# PCB_Draft_1.net
KiCad netlist of a schematic drawn in EAGLE
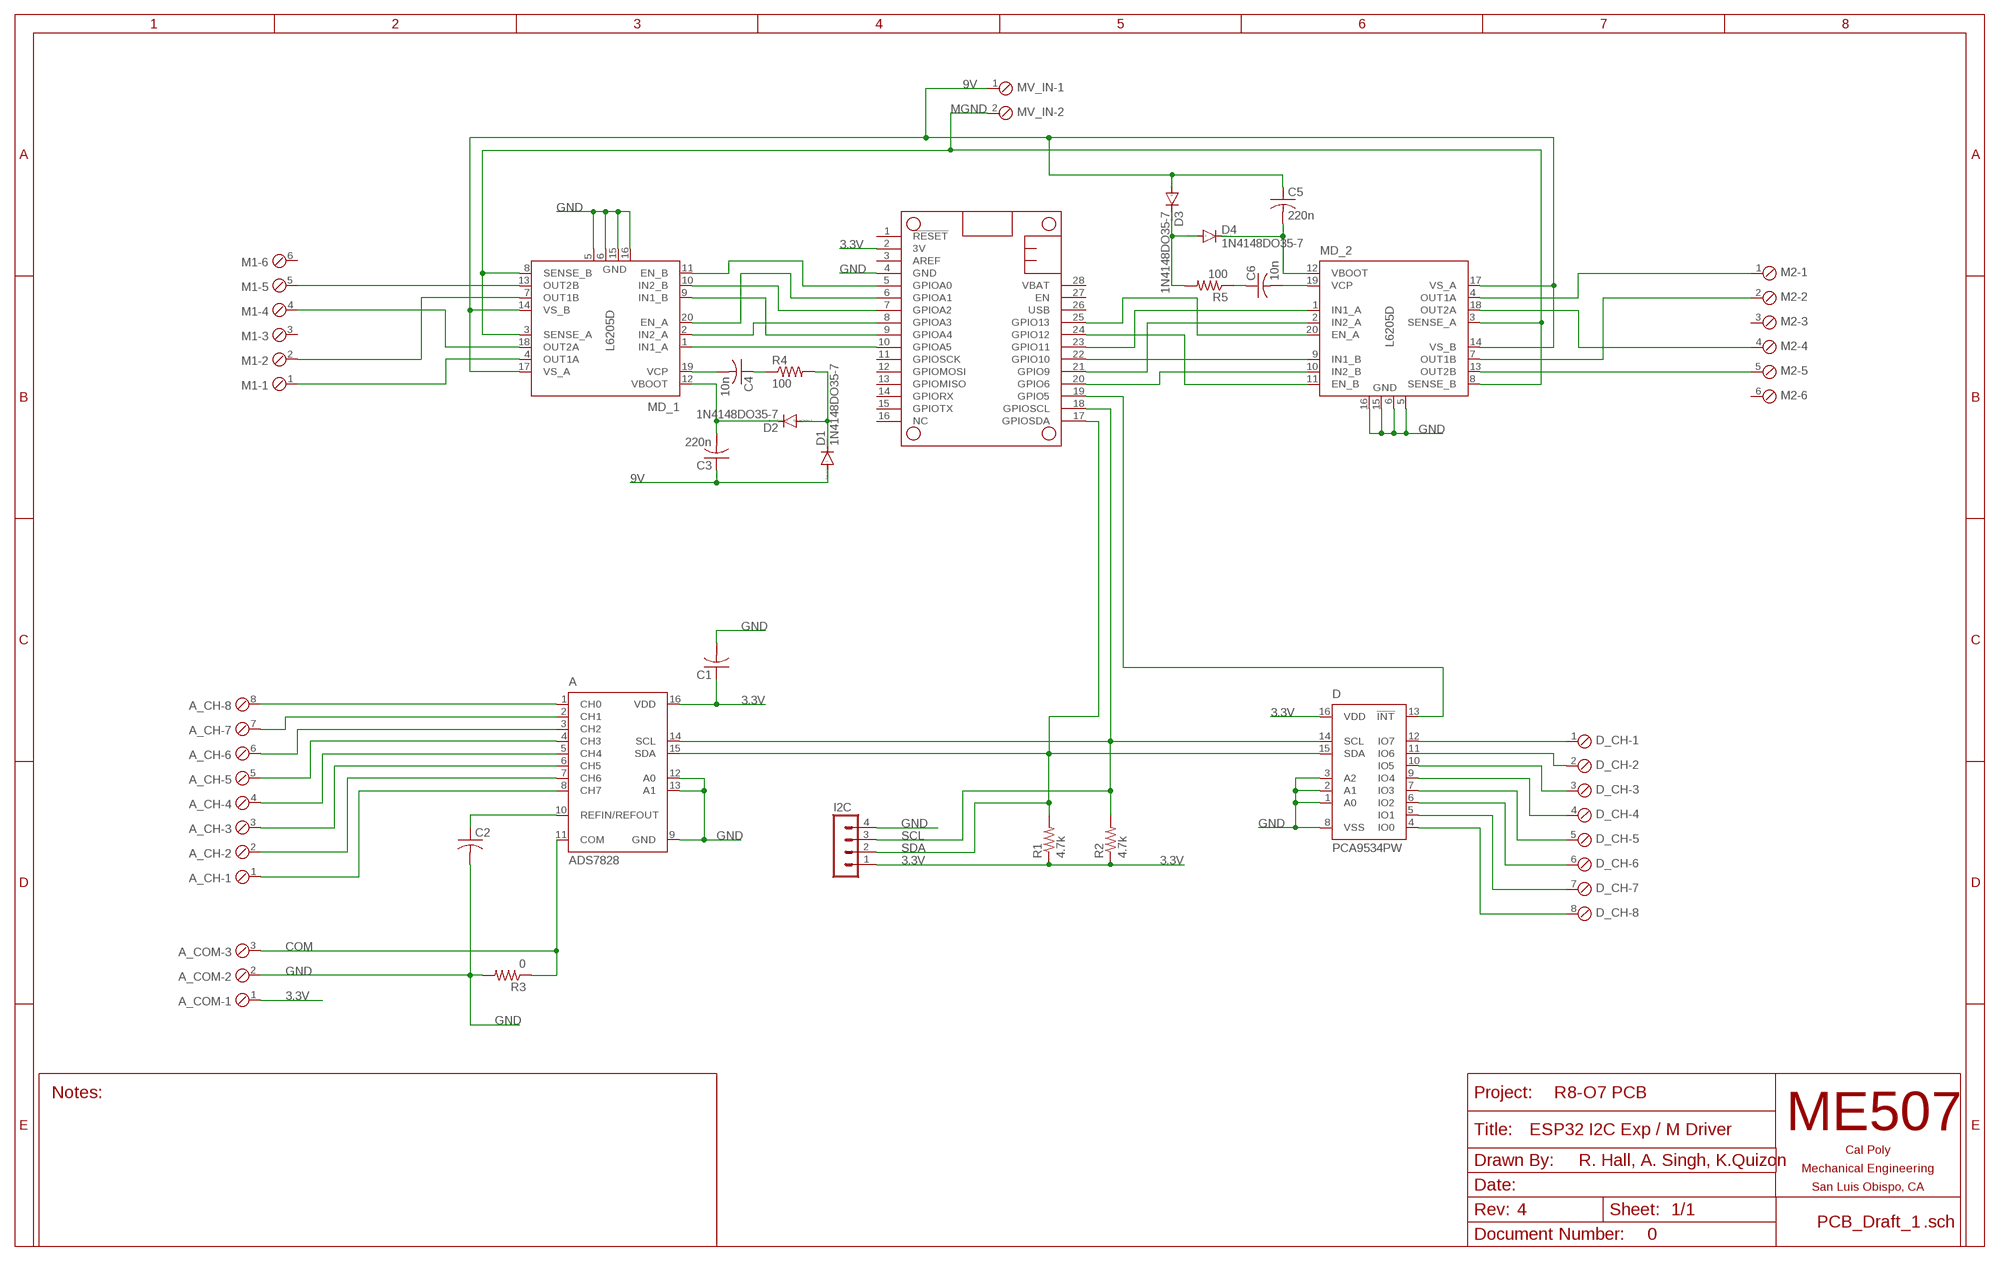
[diagram p0: schematic, sheet 1]

(export (version "E")
  (design (tool "Eeschema 10.0.6"))
  (components
    (comp (ref "A")
      (value "ADS7828")
      (footprint "eagle-import:TSSOP16-PW")
      (fields (field (name "MF") "TEXAS INSTRUMENTS") (field (name "MPN") "ADS7828E/250"))
      (libsource (lib "eagle-import") (part "ADS7828"))
    )
    (comp (ref "A_CH")
      (value "SCREWTERM_8P_254")
      (footprint "eagle-import:8POL254")
      (libsource (lib "eagle-import") (part "SCREWTERM_8P_254"))
    )
    (comp (ref "A_COM")
      (value "SCREWTERM_3P_254")
      (footprint "eagle-import:3POL254")
      (libsource (lib "eagle-import") (part "SCREWTERM_3P_254"))
    )
    (comp (ref "C1")
      (value "C-USC0805")
      (footprint "eagle-import:C0805")
      (libsource (lib "eagle-import") (part "C-USC0805"))
    )
    (comp (ref "C2")
      (value "C-USC0805")
      (footprint "eagle-import:C0805")
      (libsource (lib "eagle-import") (part "C-USC0805"))
    )
    (comp (ref "C3")
      (value "220n")
      (footprint "eagle-import:C0805")
      (libsource (lib "eagle-import") (part "C-USC0805"))
    )
    (comp (ref "C4")
      (value "10n")
      (footprint "eagle-import:C0805")
      (libsource (lib "eagle-import") (part "C-USC0805"))
    )
    (comp (ref "C5")
      (value "220n")
      (footprint "eagle-import:C0805")
      (libsource (lib "eagle-import") (part "C-USC0805"))
    )
    (comp (ref "C6")
      (value "10n")
      (footprint "eagle-import:C0805")
      (libsource (lib "eagle-import") (part "C-USC0805"))
    )
    (comp (ref "D")
      (value "PCA9534PW")
      (footprint "eagle-import:TSSOP16")
      (libsource (lib "eagle-import") (part "PCA9534PW"))
    )
    (comp (ref "D1")
      (value "1N4148DO35-7")
      (footprint "eagle-import:DO35-7")
      (libsource (lib "eagle-import") (part "1N4148DO35-7"))
    )
    (comp (ref "D2")
      (value "1N4148DO35-7")
      (footprint "eagle-import:DO35-7")
      (libsource (lib "eagle-import") (part "1N4148DO35-7"))
    )
    (comp (ref "D3")
      (value "1N4148DO35-7")
      (footprint "eagle-import:DO35-7")
      (libsource (lib "eagle-import") (part "1N4148DO35-7"))
    )
    (comp (ref "D4")
      (value "1N4148DO35-7")
      (footprint "eagle-import:DO35-7")
      (libsource (lib "eagle-import") (part "1N4148DO35-7"))
    )
    (comp (ref "D_CH")
      (value "SCREWTERM_8P_254")
      (footprint "eagle-import:8POL254")
      (libsource (lib "eagle-import") (part "SCREWTERM_8P_254"))
    )
    (comp (ref "FTHRWNG")
      (value "FEATHERWINGEXTENDED_BOTH_ENDS")
      (footprint "eagle-import:FEATHERWING")
      (libsource (lib "eagle-import") (part "FEATHERWINGEXTENDED_BOTH_ENDS"))
    )
    (comp (ref "I2C")
      (value "MA04-1")
      (footprint "eagle-import:MA04-1")
      (libsource (lib "eagle-import") (part "MA04-1"))
    )
    (comp (ref "M1")
      (value "SCREWTERM_6P_254")
      (footprint "eagle-import:6POL254")
      (libsource (lib "eagle-import") (part "SCREWTERM_6P_254"))
    )
    (comp (ref "M2")
      (value "SCREWTERM_6P_254")
      (footprint "eagle-import:6POL254")
      (libsource (lib "eagle-import") (part "SCREWTERM_6P_254"))
    )
    (comp (ref "MD_1")
      (value "L6205D")
      (footprint "eagle-import:SO20")
      (libsource (lib "eagle-import") (part "L6205D"))
    )
    (comp (ref "MD_2")
      (value "L6205D")
      (footprint "eagle-import:SO20")
      (libsource (lib "eagle-import") (part "L6205D"))
    )
    (comp (ref "MV_IN")
      (value "SCREWTERM_2P_254")
      (footprint "eagle-import:2POL254")
      (libsource (lib "eagle-import") (part "SCREWTERM_2P_254"))
    )
    (comp (ref "R1")
      (value "4.7k")
      (footprint "eagle-import:M0805")
      (libsource (lib "eagle-import") (part "R-US_M0805"))
    )
    (comp (ref "R2")
      (value "4.7k")
      (footprint "eagle-import:M0805")
      (libsource (lib "eagle-import") (part "R-US_M0805"))
    )
    (comp (ref "R3")
      (value "0")
      (footprint "eagle-import:M0805")
      (libsource (lib "eagle-import") (part "R-US_M0805"))
    )
    (comp (ref "R4")
      (value "100")
      (footprint "eagle-import:M0805")
      (libsource (lib "eagle-import") (part "R-US_M0805"))
    )
    (comp (ref "R5")
      (value "100")
      (footprint "eagle-import:M0805")
      (libsource (lib "eagle-import") (part "R-US_M0805"))
    )
  )
  (nets
    (net (code "1") (name "/3.3V") (class "Default")
      (node (ref "A") (pin "16") (pinfunction "VDD_16") (pintype "power_in"))
      (node (ref "A_COM") (pin "1") (pinfunction "1_1") (pintype "passive"))
      (node (ref "C1") (pin "1") (pinfunction "1_1") (pintype "passive"))
      (node (ref "D") (pin "16") (pinfunction "VDD_16") (pintype "power_in"))
      (node (ref "FTHRWNG") (pin "2") (pinfunction "3V_2") (pintype "power_in"))
      (node (ref "I2C") (pin "1") (pinfunction "1_1") (pintype "passive"))
      (node (ref "R1") (pin "1") (pinfunction "1_1") (pintype "passive"))
      (node (ref "R2") (pin "1") (pinfunction "1_1") (pintype "passive"))
    )
    (net (code "2") (name "/9V") (class "Default")
      (node (ref "C3") (pin "1") (pinfunction "1_1") (pintype "passive"))
      (node (ref "C5") (pin "1") (pinfunction "1_1") (pintype "passive"))
      (node (ref "D1") (pin "A") (pinfunction "A_A") (pintype "passive"))
      (node (ref "D3") (pin "A") (pinfunction "A_A") (pintype "passive"))
      (node (ref "MD_1") (pin "14") (pinfunction "VS_B_14") (pintype "power_in"))
      (node (ref "MD_1") (pin "17") (pinfunction "VS_A_17") (pintype "power_in"))
      (node (ref "MD_2") (pin "14") (pinfunction "VS_B_14") (pintype "power_in"))
      (node (ref "MD_2") (pin "17") (pinfunction "VS_A_17") (pintype "power_in"))
      (node (ref "MV_IN") (pin "1") (pinfunction "1_1") (pintype "passive"))
    )
    (net (code "3") (name "/COM") (class "Default")
      (node (ref "A") (pin "11") (pinfunction "COM_11") (pintype "input"))
      (node (ref "A_COM") (pin "3") (pinfunction "1_3") (pintype "passive"))
      (node (ref "R3") (pin "1") (pinfunction "1_1") (pintype "passive"))
    )
    (net (code "4") (name "/GND") (class "Default")
      (node (ref "A") (pin "12") (pinfunction "A0_12") (pintype "input"))
      (node (ref "A") (pin "13") (pinfunction "A1_13") (pintype "input"))
      (node (ref "A") (pin "9") (pinfunction "GND_9") (pintype "power_in"))
      (node (ref "A_COM") (pin "2") (pinfunction "1_2") (pintype "passive"))
      (node (ref "C1") (pin "2") (pinfunction "2_2") (pintype "passive"))
      (node (ref "C2") (pin "2") (pinfunction "2_2") (pintype "passive"))
      (node (ref "D") (pin "1") (pinfunction "A0_1") (pintype "input"))
      (node (ref "D") (pin "2") (pinfunction "A1_2") (pintype "input"))
      (node (ref "D") (pin "3") (pinfunction "A2_3") (pintype "input"))
      (node (ref "D") (pin "8") (pinfunction "VSS_8") (pintype "power_in"))
      (node (ref "FTHRWNG") (pin "4") (pinfunction "GND_4") (pintype "power_in"))
      (node (ref "I2C") (pin "4") (pinfunction "4_4") (pintype "passive"))
      (node (ref "MD_1") (pin "15") (pinfunction "GND_15") (pintype "power_in"))
      (node (ref "MD_1") (pin "16") (pinfunction "GND_16") (pintype "power_in"))
      (node (ref "MD_1") (pin "5") (pinfunction "GND_5") (pintype "power_in"))
      (node (ref "MD_1") (pin "6") (pinfunction "GND_6") (pintype "power_in"))
      (node (ref "MD_2") (pin "15") (pinfunction "GND_15") (pintype "power_in"))
      (node (ref "MD_2") (pin "16") (pinfunction "GND_16") (pintype "power_in"))
      (node (ref "MD_2") (pin "5") (pinfunction "GND_5") (pintype "power_in"))
      (node (ref "MD_2") (pin "6") (pinfunction "GND_6") (pintype "power_in"))
      (node (ref "R3") (pin "2") (pinfunction "2_2") (pintype "passive"))
    )
    (net (code "5") (name "/MGND") (class "Default")
      (node (ref "MD_1") (pin "3") (pinfunction "SENSE_A_3") (pintype "input"))
      (node (ref "MD_1") (pin "8") (pinfunction "SENSE_B_8") (pintype "input"))
      (node (ref "MD_2") (pin "3") (pinfunction "SENSE_A_3") (pintype "input"))
      (node (ref "MD_2") (pin "8") (pinfunction "SENSE_B_8") (pintype "input"))
      (node (ref "MV_IN") (pin "2") (pinfunction "1_2") (pintype "passive"))
    )
    (net (code "6") (name "/SCL") (class "Default")
      (node (ref "A") (pin "14") (pinfunction "SCL_14") (pintype "input"))
      (node (ref "D") (pin "14") (pinfunction "SCL_14") (pintype "input"))
      (node (ref "FTHRWNG") (pin "18") (pinfunction "GPIOSCL_18") (pintype "bidirectional"))
      (node (ref "I2C") (pin "3") (pinfunction "3_3") (pintype "passive"))
      (node (ref "R2") (pin "2") (pinfunction "2_2") (pintype "passive"))
    )
    (net (code "7") (name "/SDA") (class "Default")
      (node (ref "A") (pin "15") (pinfunction "SDA_15") (pintype "bidirectional"))
      (node (ref "D") (pin "15") (pinfunction "SDA_15") (pintype "bidirectional"))
      (node (ref "FTHRWNG") (pin "17") (pinfunction "GPIOSDA_17") (pintype "bidirectional"))
      (node (ref "I2C") (pin "2") (pinfunction "2_2") (pintype "passive"))
      (node (ref "R1") (pin "2") (pinfunction "2_2") (pintype "passive"))
    )
    (net (code "8") (name "/USB") (class "Default")
      (node (ref "FTHRWNG") (pin "26") (pinfunction "USB_26") (pintype "power_in"))
    )
    (net (code "9") (name "/VBAT") (class "Default")
      (node (ref "FTHRWNG") (pin "28") (pinfunction "VBAT_28") (pintype "power_in"))
    )
    (net (code "10") (name "Net-(A-CH0)") (class "Default")
      (node (ref "A") (pin "1") (pinfunction "CH0_1") (pintype "input"))
      (node (ref "A_CH") (pin "8") (pinfunction "1_8") (pintype "passive"))
    )
    (net (code "11") (name "Net-(A-CH1)") (class "Default")
      (node (ref "A") (pin "2") (pinfunction "CH1_2") (pintype "input"))
      (node (ref "A_CH") (pin "7") (pinfunction "1_7") (pintype "passive"))
    )
    (net (code "12") (name "Net-(A-CH2)") (class "Default")
      (node (ref "A") (pin "3") (pinfunction "CH2_3") (pintype "input"))
      (node (ref "A_CH") (pin "6") (pinfunction "1_6") (pintype "passive"))
    )
    (net (code "13") (name "Net-(A-CH3)") (class "Default")
      (node (ref "A") (pin "4") (pinfunction "CH3_4") (pintype "input"))
      (node (ref "A_CH") (pin "5") (pinfunction "1_5") (pintype "passive"))
    )
    (net (code "14") (name "Net-(A-CH4)") (class "Default")
      (node (ref "A") (pin "5") (pinfunction "CH4_5") (pintype "input"))
      (node (ref "A_CH") (pin "4") (pinfunction "1_4") (pintype "passive"))
    )
    (net (code "15") (name "Net-(A-CH5)") (class "Default")
      (node (ref "A") (pin "6") (pinfunction "CH5_6") (pintype "input"))
      (node (ref "A_CH") (pin "3") (pinfunction "1_3") (pintype "passive"))
    )
    (net (code "16") (name "Net-(A-CH6)") (class "Default")
      (node (ref "A") (pin "7") (pinfunction "CH6_7") (pintype "input"))
      (node (ref "A_CH") (pin "2") (pinfunction "1_2") (pintype "passive"))
    )
    (net (code "17") (name "Net-(A-CH7)") (class "Default")
      (node (ref "A") (pin "8") (pinfunction "CH7_8") (pintype "input"))
      (node (ref "A_CH") (pin "1") (pinfunction "1_1") (pintype "passive"))
    )
    (net (code "18") (name "Net-(A-REFIN{slash}REFOUT)") (class "Default")
      (node (ref "A") (pin "10") (pinfunction "REFIN/REFOUT_10") (pintype "passive"))
      (node (ref "C2") (pin "1") (pinfunction "1_1") (pintype "passive"))
    )
    (net (code "19") (name "Net-(C4-Pad1)") (class "Default")
      (node (ref "C4") (pin "1") (pinfunction "1_1") (pintype "passive"))
      (node (ref "R4") (pin "1") (pinfunction "1_1") (pintype "passive"))
    )
    (net (code "20") (name "Net-(C6-Pad1)") (class "Default")
      (node (ref "C6") (pin "1") (pinfunction "1_1") (pintype "passive"))
      (node (ref "R5") (pin "1") (pinfunction "1_1") (pintype "passive"))
    )
    (net (code "21") (name "Net-(D-IO0)") (class "Default")
      (node (ref "D") (pin "4") (pinfunction "IO0_4") (pintype "bidirectional"))
      (node (ref "D_CH") (pin "8") (pinfunction "1_8") (pintype "passive"))
    )
    (net (code "22") (name "Net-(D-IO1)") (class "Default")
      (node (ref "D") (pin "5") (pinfunction "IO1_5") (pintype "bidirectional"))
      (node (ref "D_CH") (pin "7") (pinfunction "1_7") (pintype "passive"))
    )
    (net (code "23") (name "Net-(D-IO2)") (class "Default")
      (node (ref "D") (pin "6") (pinfunction "IO2_6") (pintype "bidirectional"))
      (node (ref "D_CH") (pin "6") (pinfunction "1_6") (pintype "passive"))
    )
    (net (code "24") (name "Net-(D-IO3)") (class "Default")
      (node (ref "D") (pin "7") (pinfunction "IO3_7") (pintype "bidirectional"))
      (node (ref "D_CH") (pin "5") (pinfunction "1_5") (pintype "passive"))
    )
    (net (code "25") (name "Net-(D-IO4)") (class "Default")
      (node (ref "D") (pin "9") (pinfunction "IO4_9") (pintype "bidirectional"))
      (node (ref "D_CH") (pin "4") (pinfunction "1_4") (pintype "passive"))
    )
    (net (code "26") (name "Net-(D-IO5)") (class "Default")
      (node (ref "D") (pin "10") (pinfunction "IO5_10") (pintype "bidirectional"))
      (node (ref "D_CH") (pin "3") (pinfunction "1_3") (pintype "passive"))
    )
    (net (code "27") (name "Net-(D-IO6)") (class "Default")
      (node (ref "D") (pin "11") (pinfunction "IO6_11") (pintype "bidirectional"))
      (node (ref "D_CH") (pin "2") (pinfunction "1_2") (pintype "passive"))
    )
    (net (code "28") (name "Net-(D-IO7)") (class "Default")
      (node (ref "D") (pin "12") (pinfunction "IO7_12") (pintype "bidirectional"))
      (node (ref "D_CH") (pin "1") (pinfunction "1_1") (pintype "passive"))
    )
    (net (code "29") (name "Net-(D-~{INT})") (class "Default")
      (node (ref "D") (pin "13") (pinfunction "~{INT}_13") (pintype "open_collector"))
      (node (ref "FTHRWNG") (pin "19") (pinfunction "GPIO5_19") (pintype "bidirectional"))
    )
    (net (code "30") (name "Net-(D1-PadC)") (class "Default")
      (node (ref "D1") (pin "C") (pinfunction "C_C") (pintype "passive"))
      (node (ref "D2") (pin "A") (pinfunction "A_A") (pintype "passive"))
      (node (ref "R4") (pin "2") (pinfunction "2_2") (pintype "passive"))
    )
    (net (code "31") (name "Net-(D3-PadC)") (class "Default")
      (node (ref "D3") (pin "C") (pinfunction "C_C") (pintype "passive"))
      (node (ref "D4") (pin "A") (pinfunction "A_A") (pintype "passive"))
      (node (ref "R5") (pin "2") (pinfunction "2_2") (pintype "passive"))
    )
    (net (code "32") (name "Net-(FTHRWNG-GPIO6)") (class "Default")
      (node (ref "FTHRWNG") (pin "20") (pinfunction "GPIO6_20") (pintype "bidirectional"))
      (node (ref "MD_2") (pin "10") (pinfunction "IN2_B_10") (pintype "input"))
    )
    (net (code "33") (name "Net-(FTHRWNG-GPIO9)") (class "Default")
      (node (ref "FTHRWNG") (pin "21") (pinfunction "GPIO9_21") (pintype "bidirectional"))
      (node (ref "MD_2") (pin "2") (pinfunction "IN2_A_2") (pintype "input"))
    )
    (net (code "34") (name "Net-(FTHRWNG-GPIO10)") (class "Default")
      (node (ref "FTHRWNG") (pin "22") (pinfunction "GPIO10_22") (pintype "bidirectional"))
      (node (ref "MD_2") (pin "9") (pinfunction "IN1_B_9") (pintype "input"))
    )
    (net (code "35") (name "Net-(FTHRWNG-GPIO11)") (class "Default")
      (node (ref "FTHRWNG") (pin "23") (pinfunction "GPIO11_23") (pintype "bidirectional"))
      (node (ref "MD_2") (pin "1") (pinfunction "IN1_A_1") (pintype "input"))
    )
    (net (code "36") (name "Net-(FTHRWNG-GPIO12)") (class "Default")
      (node (ref "FTHRWNG") (pin "24") (pinfunction "GPIO12_24") (pintype "bidirectional"))
      (node (ref "MD_2") (pin "11") (pinfunction "EN_B_11") (pintype "input"))
    )
    (net (code "37") (name "Net-(FTHRWNG-GPIO13)") (class "Default")
      (node (ref "FTHRWNG") (pin "25") (pinfunction "GPIO13_25") (pintype "bidirectional"))
      (node (ref "MD_2") (pin "20") (pinfunction "EN_A_20") (pintype "input"))
    )
    (net (code "38") (name "Net-(FTHRWNG-GPIOA0)") (class "Default")
      (node (ref "FTHRWNG") (pin "5") (pinfunction "GPIOA0_5") (pintype "bidirectional"))
      (node (ref "MD_1") (pin "11") (pinfunction "EN_B_11") (pintype "input"))
    )
    (net (code "39") (name "Net-(FTHRWNG-GPIOA1)") (class "Default")
      (node (ref "FTHRWNG") (pin "6") (pinfunction "GPIOA1_6") (pintype "bidirectional"))
      (node (ref "MD_1") (pin "20") (pinfunction "EN_A_20") (pintype "input"))
    )
    (net (code "40") (name "Net-(FTHRWNG-GPIOA2)") (class "Default")
      (node (ref "FTHRWNG") (pin "7") (pinfunction "GPIOA2_7") (pintype "bidirectional"))
      (node (ref "MD_1") (pin "10") (pinfunction "IN2_B_10") (pintype "input"))
    )
    (net (code "41") (name "Net-(FTHRWNG-GPIOA3)") (class "Default")
      (node (ref "FTHRWNG") (pin "8") (pinfunction "GPIOA3_8") (pintype "bidirectional"))
      (node (ref "MD_1") (pin "2") (pinfunction "IN2_A_2") (pintype "input"))
    )
    (net (code "42") (name "Net-(FTHRWNG-GPIOA4)") (class "Default")
      (node (ref "FTHRWNG") (pin "9") (pinfunction "GPIOA4_9") (pintype "bidirectional"))
      (node (ref "MD_1") (pin "9") (pinfunction "IN1_B_9") (pintype "input"))
    )
    (net (code "43") (name "Net-(FTHRWNG-GPIOA5)") (class "Default")
      (node (ref "FTHRWNG") (pin "10") (pinfunction "GPIOA5_10") (pintype "bidirectional"))
      (node (ref "MD_1") (pin "1") (pinfunction "IN1_A_1") (pintype "input"))
    )
    (net (code "44") (name "Net-(M1B-1)") (class "Default")
      (node (ref "M1") (pin "2") (pinfunction "1_2") (pintype "passive"))
      (node (ref "MD_1") (pin "7") (pinfunction "OUT1B_7") (pintype "output"))
    )
    (net (code "45") (name "Net-(M1D-1)") (class "Default")
      (node (ref "M1") (pin "4") (pinfunction "1_4") (pintype "passive"))
      (node (ref "MD_1") (pin "18") (pinfunction "OUT2A_18") (pintype "output"))
    )
    (net (code "46") (name "Net-(M1E-1)") (class "Default")
      (node (ref "M1") (pin "5") (pinfunction "1_5") (pintype "passive"))
      (node (ref "MD_1") (pin "13") (pinfunction "OUT2B_13") (pintype "output"))
    )
    (net (code "47") (name "Net-(M2B-1)") (class "Default")
      (node (ref "M2") (pin "2") (pinfunction "1_2") (pintype "passive"))
      (node (ref "MD_2") (pin "7") (pinfunction "OUT1B_7") (pintype "output"))
    )
    (net (code "48") (name "Net-(M2D-1)") (class "Default")
      (node (ref "M2") (pin "4") (pinfunction "1_4") (pintype "passive"))
      (node (ref "MD_2") (pin "18") (pinfunction "OUT2A_18") (pintype "output"))
    )
    (net (code "49") (name "Net-(M2E-1)") (class "Default")
      (node (ref "M2") (pin "5") (pinfunction "1_5") (pintype "passive"))
      (node (ref "MD_2") (pin "13") (pinfunction "OUT2B_13") (pintype "output"))
    )
    (net (code "50") (name "Net-(MD_1-OUT1A)") (class "Default")
      (node (ref "M1") (pin "1") (pinfunction "1_1") (pintype "passive"))
      (node (ref "MD_1") (pin "4") (pinfunction "OUT1A_4") (pintype "output"))
    )
    (net (code "51") (name "Net-(MD_1-VBOOT)") (class "Default")
      (node (ref "C3") (pin "2") (pinfunction "2_2") (pintype "passive"))
      (node (ref "D2") (pin "C") (pinfunction "C_C") (pintype "passive"))
      (node (ref "MD_1") (pin "12") (pinfunction "VBOOT_12") (pintype "power_in"))
    )
    (net (code "52") (name "Net-(MD_1-VCP)") (class "Default")
      (node (ref "C4") (pin "2") (pinfunction "2_2") (pintype "passive"))
      (node (ref "MD_1") (pin "19") (pinfunction "VCP_19") (pintype "power_in"))
    )
    (net (code "53") (name "Net-(MD_2-OUT1A)") (class "Default")
      (node (ref "M2") (pin "1") (pinfunction "1_1") (pintype "passive"))
      (node (ref "MD_2") (pin "4") (pinfunction "OUT1A_4") (pintype "output"))
    )
    (net (code "54") (name "Net-(MD_2-VBOOT)") (class "Default")
      (node (ref "C5") (pin "2") (pinfunction "2_2") (pintype "passive"))
      (node (ref "D4") (pin "C") (pinfunction "C_C") (pintype "passive"))
      (node (ref "MD_2") (pin "12") (pinfunction "VBOOT_12") (pintype "power_in"))
    )
    (net (code "55") (name "Net-(MD_2-VCP)") (class "Default")
      (node (ref "C6") (pin "2") (pinfunction "2_2") (pintype "passive"))
      (node (ref "MD_2") (pin "19") (pinfunction "VCP_19") (pintype "power_in"))
    )
    (net (code "56") (name "unconnected-(FTHRWNG-AREF-Pad3)") (class "Default")
      (node (ref "FTHRWNG") (pin "3") (pinfunction "AREF_3") (pintype "passive"))
    )
    (net (code "57") (name "unconnected-(FTHRWNG-EN-Pad27)") (class "Default")
      (node (ref "FTHRWNG") (pin "27") (pinfunction "EN_27") (pintype "passive"))
    )
    (net (code "58") (name "unconnected-(FTHRWNG-GPIOMISO-Pad13)") (class "Default")
      (node (ref "FTHRWNG") (pin "13") (pinfunction "GPIOMISO_13") (pintype "bidirectional"))
    )
    (net (code "59") (name "unconnected-(FTHRWNG-GPIOMOSI-Pad12)") (class "Default")
      (node (ref "FTHRWNG") (pin "12") (pinfunction "GPIOMOSI_12") (pintype "bidirectional"))
    )
    (net (code "60") (name "unconnected-(FTHRWNG-GPIORX-Pad14)") (class "Default")
      (node (ref "FTHRWNG") (pin "14") (pinfunction "GPIORX_14") (pintype "bidirectional"))
    )
    (net (code "61") (name "unconnected-(FTHRWNG-GPIOSCK-Pad11)") (class "Default")
      (node (ref "FTHRWNG") (pin "11") (pinfunction "GPIOSCK_11") (pintype "bidirectional"))
    )
    (net (code "62") (name "unconnected-(FTHRWNG-GPIOTX-Pad15)") (class "Default")
      (node (ref "FTHRWNG") (pin "15") (pinfunction "GPIOTX_15") (pintype "bidirectional"))
    )
    (net (code "63") (name "unconnected-(FTHRWNG-NC-Pad16)") (class "Default")
      (node (ref "FTHRWNG") (pin "16") (pinfunction "NC_16") (pintype "passive"))
    )
    (net (code "64") (name "unconnected-(FTHRWNG-~{RESET}-Pad1)") (class "Default")
      (node (ref "FTHRWNG") (pin "1") (pinfunction "~{RESET}_1") (pintype "input"))
    )
    (net (code "65") (name "unconnected-(M1C-1-Pad3)") (class "Default")
      (node (ref "M1") (pin "3") (pinfunction "1_3") (pintype "passive"))
    )
    (net (code "66") (name "unconnected-(M1F-1-Pad6)") (class "Default")
      (node (ref "M1") (pin "6") (pinfunction "1_6") (pintype "passive"))
    )
    (net (code "67") (name "unconnected-(M2C-1-Pad3)") (class "Default")
      (node (ref "M2") (pin "3") (pinfunction "1_3") (pintype "passive"))
    )
    (net (code "68") (name "unconnected-(M2F-1-Pad6)") (class "Default")
      (node (ref "M2") (pin "6") (pinfunction "1_6") (pintype "passive"))
    )
  )
)
